# ST_LINK_V2-1.net
KiCad netlist of a schematic drawn in Altium Designer
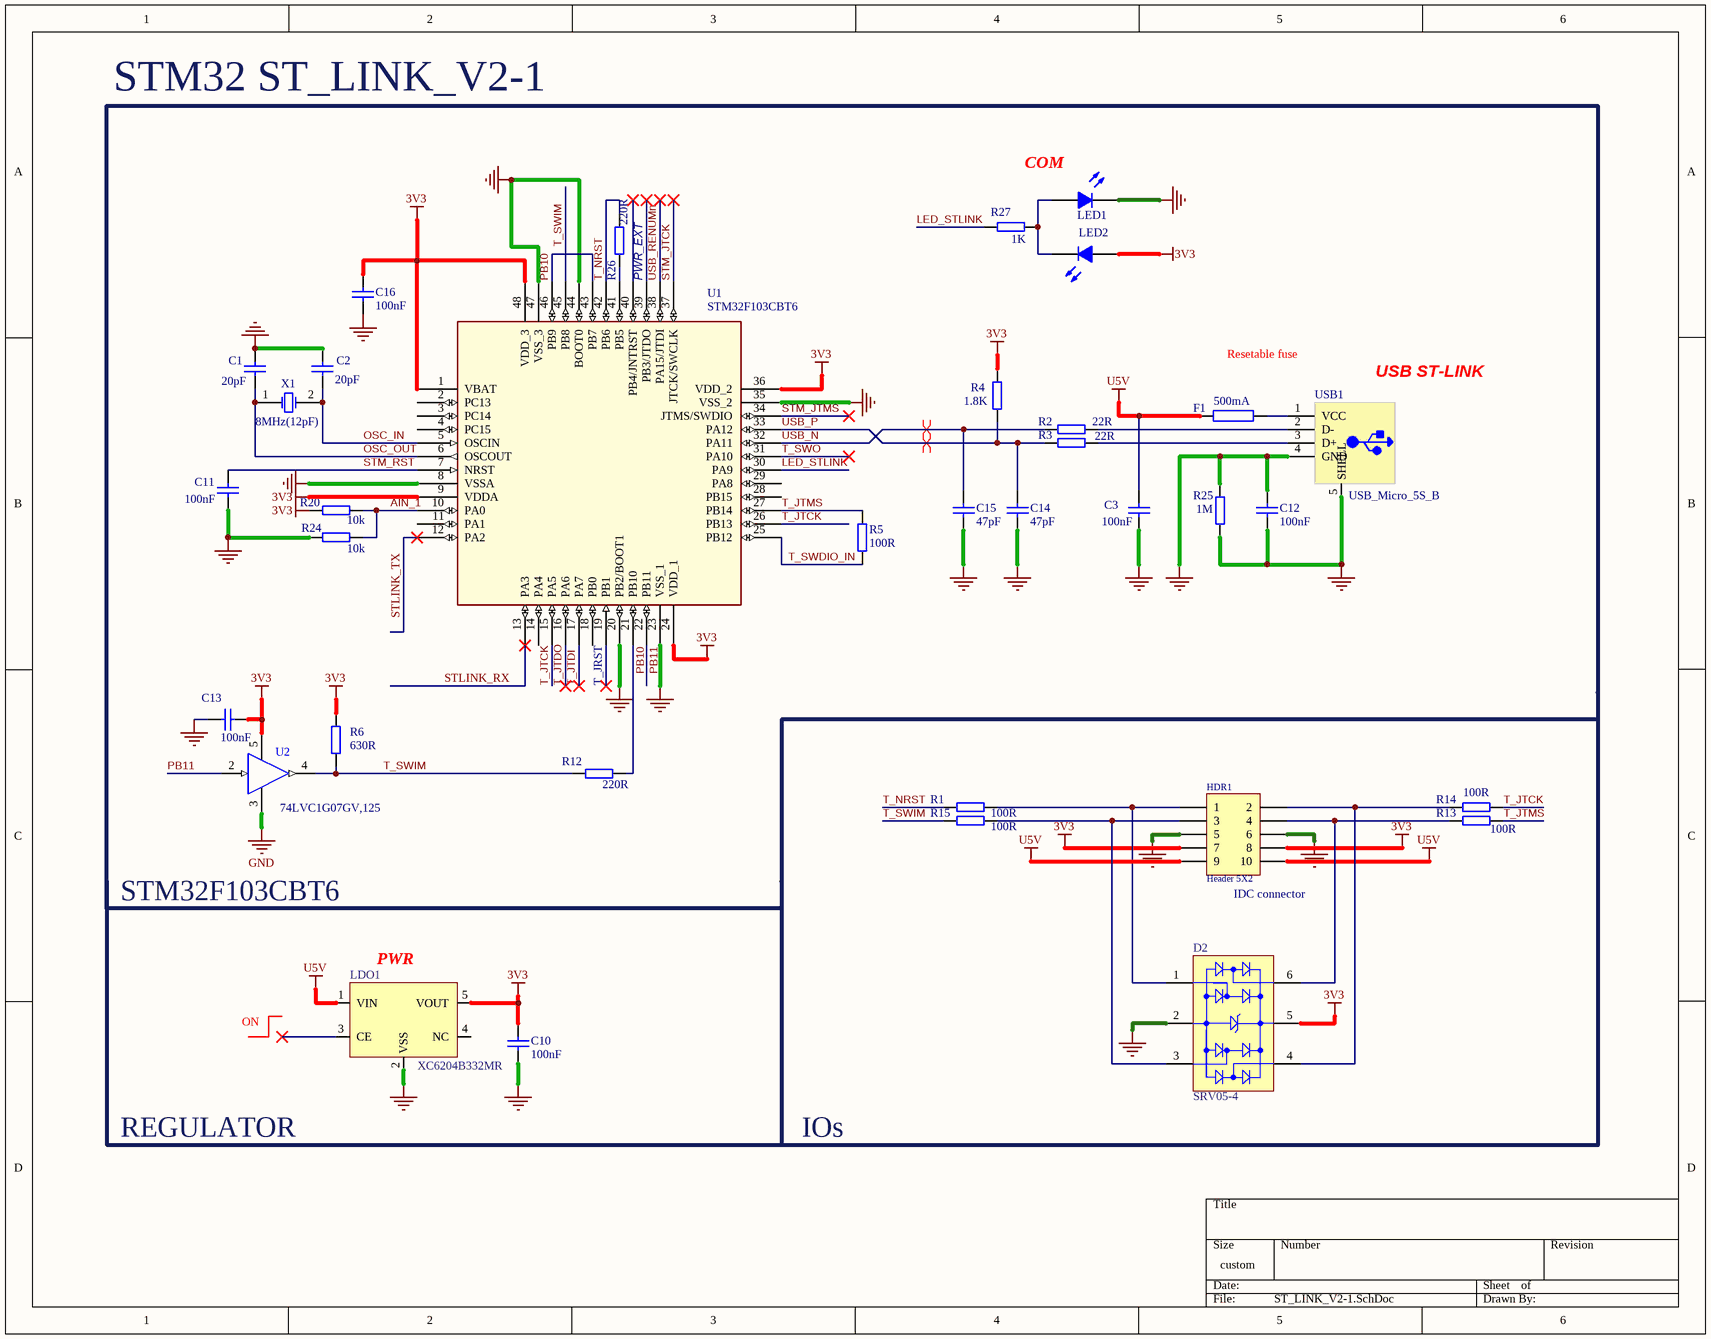
[diagram p0: ST_LINK_V2-1.SchDoc]

(export (version "E")
  (design (tool "Eeschema 10.0.6"))
  (components
    (comp (ref "C1")
      (value "20pF")
      (footprint "C0603-NO")
      (description "Capacitor, X5R, ±10%, 6.3V")
      (fields
        (field (name "PART NUMBER") "C0603-N.C.")
        (field (name "MANUFACTURER") "N.A.")
        (field (name "PUBLISHER") "Nordic Semiconductor")
      )
      (libsource (lib "adafruit") (part "Cap_0603"))
    )
    (comp (ref "C2")
      (value "20pF")
      (footprint "C0603-NO")
      (description "Capacitor, X5R, ±10%, 6.3V")
      (fields
        (field (name "PART NUMBER") "C0603-N.C.")
        (field (name "MANUFACTURER") "N.A.")
        (field (name "PUBLISHER") "Nordic Semiconductor")
      )
      (libsource (lib "adafruit") (part "Cap_0603"))
    )
    (comp (ref "C3")
      (value "100nF")
      (footprint "C0603-NO")
      (description "Capacitor, X5R, ±10%, 6.3V")
      (fields
        (field (name "PART NUMBER") "C0603-N.C.")
        (field (name "MANUFACTURER") "N.A.")
        (field (name "PUBLISHER") "Nordic Semiconductor")
      )
      (libsource (lib "adafruit") (part "Cap_0603"))
    )
    (comp (ref "C10")
      (value "100nF")
      (footprint "C0603-NO")
      (description "Capacitor, X5R, ±10%, 6.3V")
      (fields
        (field (name "PART NUMBER") "C0603-N.C.")
        (field (name "MANUFACTURER") "N.A.")
        (field (name "PUBLISHER") "Nordic Semiconductor")
      )
      (libsource (lib "adafruit") (part "Cap_0603"))
    )
    (comp (ref "C11")
      (value "100nF")
      (footprint "C0603-NO")
      (description "Capacitor, X5R, ±10%, 6.3V")
      (fields
        (field (name "PART NUMBER") "C0603-N.C.")
        (field (name "MANUFACTURER") "N.A.")
        (field (name "PUBLISHER") "Nordic Semiconductor")
      )
      (libsource (lib "adafruit") (part "Cap_0603"))
    )
    (comp (ref "C12")
      (value "100nF")
      (footprint "C0603-NO")
      (description "Capacitor, X5R, ±10%, 6.3V")
      (fields
        (field (name "PART NUMBER") "C0603-N.C.")
        (field (name "MANUFACTURER") "N.A.")
        (field (name "PUBLISHER") "Nordic Semiconductor")
      )
      (libsource (lib "adafruit") (part "Cap_0603"))
    )
    (comp (ref "C13")
      (value "100nF")
      (footprint "C0603-NO")
      (description "Capacitor, X5R, ±10%, 6.3V")
      (fields
        (field (name "PART NUMBER") "C0603-N.C.")
        (field (name "MANUFACTURER") "N.A.")
        (field (name "PUBLISHER") "Nordic Semiconductor")
      )
      (libsource (lib "adafruit") (part "Cap_0603"))
    )
    (comp (ref "C14")
      (value "47pF")
      (footprint "C0603-NO")
      (description "Capacitor, X5R, ±10%, 6.3V")
      (fields
        (field (name "PART NUMBER") "C0603-N.C.")
        (field (name "MANUFACTURER") "N.A.")
        (field (name "PUBLISHER") "Nordic Semiconductor")
      )
      (libsource (lib "adafruit") (part "Cap_0603"))
    )
    (comp (ref "C15")
      (value "47pF")
      (footprint "C0603-NO")
      (description "Capacitor, X5R, ±10%, 6.3V")
      (fields
        (field (name "PART NUMBER") "C0603-N.C.")
        (field (name "MANUFACTURER") "N.A.")
        (field (name "PUBLISHER") "Nordic Semiconductor")
      )
      (libsource (lib "adafruit") (part "Cap_0603"))
    )
    (comp (ref "C16")
      (value "100nF")
      (footprint "C0603-NO")
      (description "Capacitor, X5R, ±10%, 6.3V")
      (fields
        (field (name "PART NUMBER") "C0603-N.C.")
        (field (name "MANUFACTURER") "N.A.")
        (field (name "PUBLISHER") "Nordic Semiconductor")
      )
      (libsource (lib "adafruit") (part "Cap_0603"))
    )
    (comp (ref "D2")
      (value "SRV05-4")
      (footprint "SOT23-6")
      (fields (field (name "MANUFACTURER") "MSKSEMI(美森科)"))
      (libsource (lib "adafruit") (part "SRV05-4"))
    )
    (comp (ref "F1")
      (value "500mA")
      (footprint "F1206")
      (description "Resetable fuse")
      (fields (field (name "Comment") "Resistor_FUSE"))
      (libsource (lib "adafruit") (part "Resistor_FUSE"))
    )
    (comp (ref "HDR1")
      (value "Header 5X2")
      (footprint "IDC10_2SIDED")
      (description "Header, 5-Pin, Dual row")
      (libsource (lib "adafruit") (part "Header 5X2"))
    )
    (comp (ref "LDO1")
      (value "XC6204B332MR")
      (footprint "SOT23-5L")
      (fields (field (name "MANUFACTURER") "TOREX(特瑞仕)"))
      (libsource (lib "adafruit") (part "XC6204B332MR"))
    )
    (comp (ref "LED1")
      (value "GREEN LED")
      (footprint "CHIPLED_0603 - NO")
      (description "SMD lamp beads")
      (libsource (lib "adafruit") (part "LEDCHIP-LED0603"))
    )
    (comp (ref "LED2")
      (value "BLUE LED")
      (footprint "CHIPLED_0603 - NO")
      (description "SMD lamp beads")
      (libsource (lib "adafruit") (part "LEDCHIP-LED0603"))
    )
    (comp (ref "R1")
      (value "100Ω")
      (footprint "R0603-NO")
      (description "Resistor, ±1%, 0.100W")
      (fields
        (field (name "PART NUMBER") "R0603-N.C.Ω")
        (field (name "MANUFACTURER") "N.A.")
        (field (name "PUBLISHER") "Nordic Semiconductor")
      )
      (libsource (lib "adafruit") (part "Res_0603"))
    )
    (comp (ref "R2")
      (value "22Ω")
      (footprint "R0603-NO")
      (description "Resistor, ±1%, 0.100W")
      (fields
        (field (name "PART NUMBER") "R0603-N.C.Ω")
        (field (name "MANUFACTURER") "N.A.")
        (field (name "PUBLISHER") "Nordic Semiconductor")
      )
      (libsource (lib "") (part "Res_0603_2"))
    )
    (comp (ref "R3")
      (value "22Ω")
      (footprint "R0603-NO")
      (description "Resistor, ±1%, 0.100W")
      (fields
        (field (name "PART NUMBER") "R0603-N.C.Ω")
        (field (name "MANUFACTURER") "N.A.")
        (field (name "PUBLISHER") "Nordic Semiconductor")
      )
      (libsource (lib "") (part "Res_0603_2"))
    )
    (comp (ref "R4")
      (value "1.8kΩ")
      (footprint "R0603-NO")
      (description "Resistor, ±1%, 0.100W")
      (fields
        (field (name "PART NUMBER") "R0603-N.C.Ω")
        (field (name "MANUFACTURER") "N.A.")
        (field (name "PUBLISHER") "Nordic Semiconductor")
      )
      (libsource (lib "adafruit") (part "Res_0603"))
    )
    (comp (ref "R5")
      (value "100Ω")
      (footprint "R0603-NO")
      (description "Resistor, ±1%, 0.100W")
      (fields
        (field (name "PART NUMBER") "R0603-N.C.Ω")
        (field (name "MANUFACTURER") "N.A.")
        (field (name "PUBLISHER") "Nordic Semiconductor")
      )
      (libsource (lib "") (part "Res_0603_3"))
    )
    (comp (ref "R6")
      (value "630Ω")
      (footprint "R0603-NO")
      (description "Resistor, ±1%, 0.100W")
      (fields
        (field (name "PART NUMBER") "R0603-N.C.Ω")
        (field (name "MANUFACTURER") "N.A.")
        (field (name "PUBLISHER") "Nordic Semiconductor")
      )
      (libsource (lib "") (part "Res_0603_1"))
    )
    (comp (ref "R12")
      (value "220Ω")
      (footprint "R0603-NO")
      (description "Resistor, ±1%, 0.100W")
      (fields
        (field (name "PART NUMBER") "R0603-N.C.Ω")
        (field (name "MANUFACTURER") "N.A.")
        (field (name "PUBLISHER") "Nordic Semiconductor")
      )
      (libsource (lib "") (part "Res_0603_3"))
    )
    (comp (ref "R13")
      (value "100Ω")
      (footprint "R0603-NO")
      (description "Resistor, ±1%, 0.100W")
      (fields
        (field (name "PART NUMBER") "R0603-N.C.Ω")
        (field (name "MANUFACTURER") "N.A.")
        (field (name "PUBLISHER") "Nordic Semiconductor")
      )
      (libsource (lib "") (part "Res_0603_1"))
    )
    (comp (ref "R14")
      (value "100Ω")
      (footprint "R0603-NO")
      (description "Resistor, ±1%, 0.100W")
      (fields
        (field (name "PART NUMBER") "R0603-N.C.Ω")
        (field (name "MANUFACTURER") "N.A.")
        (field (name "PUBLISHER") "Nordic Semiconductor")
      )
      (libsource (lib "") (part "Res_0603_2"))
    )
    (comp (ref "R15")
      (value "100Ω")
      (footprint "R0603-NO")
      (description "Resistor, ±1%, 0.100W")
      (fields
        (field (name "PART NUMBER") "R0603-N.C.Ω")
        (field (name "MANUFACTURER") "N.A.")
        (field (name "PUBLISHER") "Nordic Semiconductor")
      )
      (libsource (lib "") (part "Res_0603_2"))
    )
    (comp (ref "R20")
      (value "10kΩ")
      (footprint "R0603-NO")
      (description "Resistor, ±1%, 0.100W")
      (fields
        (field (name "PART NUMBER") "R0603-N.C.Ω")
        (field (name "MANUFACTURER") "N.A.")
        (field (name "PUBLISHER") "Nordic Semiconductor")
      )
      (libsource (lib "") (part "Res_0603_3"))
    )
    (comp (ref "R24")
      (value "10kΩ")
      (footprint "R0603-NO")
      (description "Resistor, ±1%, 0.100W")
      (fields
        (field (name "PART NUMBER") "R0603-N.C.Ω")
        (field (name "MANUFACTURER") "N.A.")
        (field (name "PUBLISHER") "Nordic Semiconductor")
      )
      (libsource (lib "adafruit") (part "Res_0603"))
    )
    (comp (ref "R25")
      (value "1MΩ")
      (footprint "R0603-NO")
      (description "Resistor, ±1%, 0.100W")
      (fields
        (field (name "PART NUMBER") "R0603-N.C.Ω")
        (field (name "MANUFACTURER") "N.A.")
        (field (name "PUBLISHER") "Nordic Semiconductor")
      )
      (libsource (lib "") (part "Res_0603_1"))
    )
    (comp (ref "R26")
      (value "220Ω")
      (footprint "R0603-NO")
      (description "Resistor, ±1%, 0.100W")
      (fields
        (field (name "PART NUMBER") "R0603-N.C.Ω")
        (field (name "MANUFACTURER") "N.A.")
        (field (name "PUBLISHER") "Nordic Semiconductor")
      )
      (libsource (lib "") (part "Res_0603_1"))
    )
    (comp (ref "R27")
      (value "1kΩ")
      (footprint "R0603-NO")
      (description "Resistor, ±1%, 0.100W")
      (fields
        (field (name "PART NUMBER") "R0603-N.C.Ω")
        (field (name "MANUFACTURER") "N.A.")
        (field (name "PUBLISHER") "Nordic Semiconductor")
      )
      (libsource (lib "adafruit") (part "Res_0603"))
    )
    (comp (ref "U1")
      (value "STM32F103CBT6")
      (footprint "QFP48 7X7")
      (description "Medium-density performance line ARM-based 32-bit MCU with 64KB Flash")
      (libsource (lib "Nucleo_64") (part "STM32F103CBT6"))
    )
    (comp (ref "U2")
      (value "74LVC1G07GV,125")
      (footprint "SOT23-5L")
      (fields (field (name "MANUFACTURER") "Nexperia(安世)"))
      (libsource (lib "adafruit") (part "74LVC1G07GV,125"))
    )
    (comp (ref "USB1")
      (value "USB ConnectorsUSBMINIB - Surface Mount Female Mini-B USB Connector 4UConnector: 06564   By microbuilder.euThru-hole RA Female Mini-B USB Connector 4UConnector: 18732   By ladyada.net")
      (footprint "USB-A-SMT_48037-0001")
      (fields (field (name "NAME") "USB_Micro_5S_B"))
      (libsource (lib "adafruit") (part "USB-MALE"))
    )
    (comp (ref "X1")
      (value "8MHz(12pF)")
      (footprint "XTAL1")
      (description "Crystal Oscillator")
      (fields (field (name "PUBLISHER") "Altium Limited"))
      (libsource (lib "MB963_1") (part "XTAL"))
    )
  )
  (nets
    (net (code "1") (name "/AIN_1") (class "Default")
      (node (ref "R20") (pin "2") (pinfunction "2_2") (pintype "passive"))
      (node (ref "R24") (pin "1") (pinfunction "1_1") (pintype "passive"))
      (node (ref "U1") (pin "10") (pinfunction "PA0_10") (pintype "bidirectional"))
    )
    (net (code "2") (name "/LED_STLINK") (class "Default")
      (node (ref "R27") (pin "2") (pinfunction "2_2") (pintype "passive"))
      (node (ref "U1") (pin "30") (pinfunction "PA9_30") (pintype "bidirectional"))
    )
    (net (code "3") (name "/OSC_IN") (class "Default")
      (node (ref "C2") (pin "1") (pinfunction "1_1") (pintype "passive"))
      (node (ref "U1") (pin "5") (pinfunction "OSCIN_5") (pintype "input"))
      (node (ref "X1") (pin "2") (pinfunction "OSC2_2") (pintype "passive"))
    )
    (net (code "4") (name "/OSC_OUT") (class "Default")
      (node (ref "C1") (pin "1") (pinfunction "1_1") (pintype "passive"))
      (node (ref "U1") (pin "6") (pinfunction "OSCOUT_6") (pintype "output"))
      (node (ref "X1") (pin "1") (pinfunction "OSC1_1") (pintype "passive"))
    )
    (net (code "5") (name "/PB10") (class "Default")
      (node (ref "R12") (pin "2") (pinfunction "2_2") (pintype "passive"))
      (node (ref "U1") (pin "21") (pinfunction "PB10_21") (pintype "bidirectional"))
      (node (ref "U1") (pin "43") (pinfunction "PB7_43") (pintype "bidirectional"))
      (node (ref "U1") (pin "46") (pinfunction "PB9_46") (pintype "bidirectional"))
    )
    (net (code "6") (name "/PB11") (class "Default")
      (node (ref "U1") (pin "22") (pinfunction "PB11_22") (pintype "bidirectional"))
      (node (ref "U2") (pin "2") (pinfunction "A_2") (pintype "input"))
    )
    (net (code "7") (name "/STLINK_RX") (class "Default")
      (node (ref "U1") (pin "13") (pinfunction "PA3_13") (pintype "bidirectional+no_connect"))
    )
    (net (code "8") (name "/STLINK_TX") (class "Default")
      (node (ref "U1") (pin "12") (pinfunction "PA2_12") (pintype "bidirectional+no_connect"))
    )
    (net (code "9") (name "/STM_JTCK") (class "Default")
      (node (ref "U1") (pin "37") (pinfunction "JTCK/SWCLK_37") (pintype "bidirectional+no_connect"))
    )
    (net (code "10") (name "/STM_JTMS") (class "Default")
      (node (ref "U1") (pin "34") (pinfunction "JTMS/SWDIO_34") (pintype "bidirectional+no_connect"))
    )
    (net (code "11") (name "/STM_RST") (class "Default")
      (node (ref "C11") (pin "2") (pinfunction "2_2") (pintype "passive"))
      (node (ref "U1") (pin "7") (pinfunction "NRST_7") (pintype "input"))
    )
    (net (code "12") (name "/T_JTCK") (class "Default")
      (node (ref "R14") (pin "2") (pinfunction "2_2") (pintype "passive"))
      (node (ref "U1") (pin "15") (pinfunction "PA5_15") (pintype "bidirectional"))
      (node (ref "U1") (pin "26") (pinfunction "PB13_26") (pintype "bidirectional"))
    )
    (net (code "13") (name "/T_JTDI") (class "Default")
      (node (ref "U1") (pin "17") (pinfunction "PA7_17") (pintype "bidirectional+no_connect"))
    )
    (net (code "14") (name "/T_JTDO") (class "Default")
      (node (ref "U1") (pin "16") (pinfunction "PA6_16") (pintype "bidirectional+no_connect"))
    )
    (net (code "15") (name "/T_JTMS") (class "Default")
      (node (ref "R13") (pin "1") (pinfunction "1_1") (pintype "passive"))
      (node (ref "R5") (pin "2") (pinfunction "2_2") (pintype "passive"))
      (node (ref "U1") (pin "27") (pinfunction "PB14_27") (pintype "bidirectional"))
    )
    (net (code "16") (name "/T_NRST") (class "Default")
      (node (ref "R1") (pin "2") (pinfunction "2_2") (pintype "passive"))
      (node (ref "R26") (pin "1") (pinfunction "1_1") (pintype "passive"))
      (node (ref "U1") (pin "42") (pinfunction "PB6_42") (pintype "bidirectional"))
    )
    (net (code "17") (name "/T_SWDIO_IN") (class "Default")
      (node (ref "R5") (pin "1") (pinfunction "1_1") (pintype "passive"))
      (node (ref "U1") (pin "25") (pinfunction "PB12_25") (pintype "bidirectional"))
    )
    (net (code "18") (name "/T_SWIM") (class "Default")
      (node (ref "R12") (pin "1") (pinfunction "1_1") (pintype "passive"))
      (node (ref "R15") (pin "1") (pinfunction "1_1") (pintype "passive"))
      (node (ref "R6") (pin "2") (pinfunction "2_2") (pintype "passive"))
      (node (ref "U1") (pin "45") (pinfunction "PB8_45") (pintype "bidirectional"))
      (node (ref "U2") (pin "4") (pinfunction "Y_4") (pintype "output"))
    )
    (net (code "19") (name "/T_SWO") (class "Default")
      (node (ref "U1") (pin "31") (pinfunction "PA10_31") (pintype "bidirectional+no_connect"))
    )
    (net (code "20") (name "/USB_N") (class "Default")
      (node (ref "C15") (pin "2") (pinfunction "2_2") (pintype "passive"))
      (node (ref "R2") (pin "1") (pinfunction "1_1") (pintype "passive"))
      (node (ref "U1") (pin "32") (pinfunction "PA11_32") (pintype "bidirectional"))
    )
    (net (code "21") (name "/USB_P") (class "Default")
      (node (ref "C14") (pin "2") (pinfunction "2_2") (pintype "passive"))
      (node (ref "R3") (pin "1") (pinfunction "1_1") (pintype "passive"))
      (node (ref "R4") (pin "2") (pinfunction "2_2") (pintype "passive"))
      (node (ref "U1") (pin "33") (pinfunction "PA12_33") (pintype "bidirectional"))
    )
    (net (code "22") (name "/USB_RENUMn") (class "Default")
      (node (ref "U1") (pin "38") (pinfunction "PA15/JTDI_38") (pintype "bidirectional+no_connect"))
    )
    (net (code "23") (name "3V3") (class "Default")
      (node (ref "C10") (pin "2") (pinfunction "2_2") (pintype "passive"))
      (node (ref "C13") (pin "2") (pinfunction "2_2") (pintype "passive"))
      (node (ref "C16") (pin "2") (pinfunction "2_2") (pintype "passive"))
      (node (ref "D2") (pin "5") (pinfunction "VBUS_5") (pintype "passive"))
      (node (ref "HDR1") (pin "7") (pinfunction "7_7") (pintype "passive"))
      (node (ref "HDR1") (pin "8") (pinfunction "8_8") (pintype "passive"))
      (node (ref "LDO1") (pin "5") (pinfunction "VOUT_5") (pintype "passive"))
      (node (ref "LED2") (pin "A") (pinfunction "A_A") (pintype "passive"))
      (node (ref "R20") (pin "1") (pinfunction "1_1") (pintype "passive"))
      (node (ref "R4") (pin "1") (pinfunction "1_1") (pintype "passive"))
      (node (ref "R6") (pin "1") (pinfunction "1_1") (pintype "passive"))
      (node (ref "U1") (pin "1") (pinfunction "VBAT_1") (pintype "power_in"))
      (node (ref "U1") (pin "24") (pinfunction "VDD_1_24") (pintype "power_in"))
      (node (ref "U1") (pin "36") (pinfunction "VDD_2_36") (pintype "power_in"))
      (node (ref "U1") (pin "48") (pinfunction "VDD_3_48") (pintype "power_in"))
      (node (ref "U1") (pin "9") (pinfunction "VDDA_9") (pintype "power_in"))
      (node (ref "U2") (pin "5") (pinfunction "VCC_5") (pintype "passive"))
    )
    (net (code "24") (name "GND") (class "Default")
      (node (ref "C1") (pin "2") (pinfunction "2_2") (pintype "passive"))
      (node (ref "C10") (pin "1") (pinfunction "1_1") (pintype "passive"))
      (node (ref "C11") (pin "1") (pinfunction "1_1") (pintype "passive"))
      (node (ref "C12") (pin "1") (pinfunction "1_1") (pintype "passive"))
      (node (ref "C13") (pin "1") (pinfunction "1_1") (pintype "passive"))
      (node (ref "C14") (pin "1") (pinfunction "1_1") (pintype "passive"))
      (node (ref "C15") (pin "1") (pinfunction "1_1") (pintype "passive"))
      (node (ref "C16") (pin "1") (pinfunction "1_1") (pintype "passive"))
      (node (ref "C2") (pin "2") (pinfunction "2_2") (pintype "passive"))
      (node (ref "C3") (pin "1") (pinfunction "1_1") (pintype "passive"))
      (node (ref "D2") (pin "2") (pinfunction "GND_2") (pintype "passive"))
      (node (ref "HDR1") (pin "5") (pinfunction "5_5") (pintype "passive"))
      (node (ref "HDR1") (pin "6") (pinfunction "6_6") (pintype "passive"))
      (node (ref "LDO1") (pin "2") (pinfunction "VSS_2") (pintype "passive"))
      (node (ref "LED1") (pin "C") (pinfunction "K_C") (pintype "passive"))
      (node (ref "R24") (pin "2") (pinfunction "2_2") (pintype "passive"))
      (node (ref "R25") (pin "1") (pinfunction "1_1") (pintype "passive"))
      (node (ref "U1") (pin "20") (pinfunction "PB2/BOOT1_20") (pintype "bidirectional"))
      (node (ref "U1") (pin "23") (pinfunction "VSS_1_23") (pintype "power_in"))
      (node (ref "U1") (pin "35") (pinfunction "VSS_2_35") (pintype "power_in"))
      (node (ref "U1") (pin "44") (pinfunction "BOOT0_44") (pintype "bidirectional"))
      (node (ref "U1") (pin "47") (pinfunction "VSS_3_47") (pintype "power_in"))
      (node (ref "U1") (pin "8") (pinfunction "VSSA_8") (pintype "power_in"))
      (node (ref "U2") (pin "3") (pinfunction "GND_3") (pintype "passive"))
      (node (ref "USB1") (pin "4") (pinfunction "GND_4") (pintype "passive"))
    )
    (net (code "25") (name "GND1") (class "Default")
      (node (ref "C12") (pin "2") (pinfunction "2_2") (pintype "passive"))
      (node (ref "R25") (pin "2") (pinfunction "2_2") (pintype "passive"))
      (node (ref "USB1") (pin "5") (pinfunction "SHELL_5") (pintype "power_in"))
    )
    (net (code "26") (name "Net-(D2-I{slash}O_1)") (class "Default")
      (node (ref "D2") (pin "1") (pinfunction "I/O_1_1") (pintype "passive"))
      (node (ref "HDR1") (pin "1") (pinfunction "1_1") (pintype "passive"))
      (node (ref "R1") (pin "1") (pinfunction "1_1") (pintype "passive"))
    )
    (net (code "27") (name "Net-(D2-I{slash}O_2)") (class "Default")
      (node (ref "D2") (pin "3") (pinfunction "I/O_2_3") (pintype "passive"))
      (node (ref "HDR1") (pin "3") (pinfunction "3_3") (pintype "passive"))
      (node (ref "R15") (pin "2") (pinfunction "2_2") (pintype "passive"))
    )
    (net (code "28") (name "Net-(D2-I{slash}O_3)") (class "Default")
      (node (ref "D2") (pin "4") (pinfunction "I/O_3_4") (pintype "passive"))
      (node (ref "HDR1") (pin "2") (pinfunction "2_2") (pintype "passive"))
      (node (ref "R14") (pin "1") (pinfunction "1_1") (pintype "passive"))
    )
    (net (code "29") (name "Net-(D2-I{slash}O_4)") (class "Default")
      (node (ref "D2") (pin "6") (pinfunction "I/O_4_6") (pintype "passive"))
      (node (ref "HDR1") (pin "4") (pinfunction "4_4") (pintype "passive"))
      (node (ref "R13") (pin "2") (pinfunction "2_2") (pintype "passive"))
    )
    (net (code "30") (name "Net-(LED2-K)") (class "Default")
      (node (ref "LED1") (pin "A") (pinfunction "A_A") (pintype "passive"))
      (node (ref "LED2") (pin "C") (pinfunction "K_C") (pintype "passive"))
      (node (ref "R27") (pin "1") (pinfunction "1_1") (pintype "passive"))
    )
    (net (code "31") (name "Net-(U1-PB5)") (class "Default")
      (node (ref "R26") (pin "2") (pinfunction "2_2") (pintype "passive"))
      (node (ref "U1") (pin "41") (pinfunction "PB5_41") (pintype "bidirectional"))
    )
    (net (code "32") (name "Net-(USB1-D+)") (class "Default")
      (node (ref "R3") (pin "2") (pinfunction "2_2") (pintype "passive"))
      (node (ref "USB1") (pin "3") (pinfunction "D+_3") (pintype "passive"))
    )
    (net (code "33") (name "Net-(USB1-D-)") (class "Default")
      (node (ref "R2") (pin "2") (pinfunction "2_2") (pintype "passive"))
      (node (ref "USB1") (pin "2") (pinfunction "D-_2") (pintype "passive"))
    )
    (net (code "34") (name "Net-(USB1-VCC)") (class "Default")
      (node (ref "F1") (pin "1") (pinfunction "1_1") (pintype "passive"))
      (node (ref "USB1") (pin "1") (pinfunction "VCC_1") (pintype "power_in"))
    )
    (net (code "35") (name "U5V") (class "Default")
      (node (ref "C3") (pin "2") (pinfunction "2_2") (pintype "passive"))
      (node (ref "F1") (pin "2") (pinfunction "2_2") (pintype "passive"))
      (node (ref "HDR1") (pin "10") (pinfunction "10_10") (pintype "passive"))
      (node (ref "HDR1") (pin "9") (pinfunction "9_9") (pintype "passive"))
      (node (ref "LDO1") (pin "1") (pinfunction "VIN_1") (pintype "passive"))
    )
    (net (code "36") (name "unconnected-(LDO1-CE-Pad3)") (class "Default")
      (node (ref "LDO1") (pin "3") (pinfunction "CE_3") (pintype "passive+no_connect"))
    )
    (net (code "37") (name "unconnected-(LDO1-NC-Pad4)") (class "Default")
      (node (ref "LDO1") (pin "4") (pinfunction "NC_4") (pintype "passive"))
    )
    (net (code "38") (name "unconnected-(U1-PA1-Pad11)") (class "Default")
      (node (ref "U1") (pin "11") (pinfunction "PA1_11") (pintype "bidirectional"))
    )
    (net (code "39") (name "unconnected-(U1-PA4-Pad14)") (class "Default")
      (node (ref "U1") (pin "14") (pinfunction "PA4_14") (pintype "bidirectional"))
    )
    (net (code "40") (name "unconnected-(U1-PA8-Pad29)") (class "Default")
      (node (ref "U1") (pin "29") (pinfunction "PA8_29") (pintype "bidirectional"))
    )
    (net (code "41") (name "unconnected-(U1-PB0-Pad18)") (class "Default")
      (node (ref "U1") (pin "18") (pinfunction "PB0_18") (pintype "bidirectional"))
    )
    (net (code "42") (name "unconnected-(U1-PB1-Pad19)") (class "Default")
      (node (ref "U1") (pin "19") (pinfunction "PB1_19") (pintype "input+no_connect"))
    )
    (net (code "43") (name "unconnected-(U1-PB3{slash}JTDO-Pad39)") (class "Default")
      (node (ref "U1") (pin "39") (pinfunction "PB3/JTDO_39") (pintype "bidirectional+no_connect"))
    )
    (net (code "44") (name "unconnected-(U1-PB4{slash}JNTRST-Pad40)") (class "Default")
      (node (ref "U1") (pin "40") (pinfunction "PB4/JNTRST_40") (pintype "bidirectional+no_connect"))
    )
    (net (code "45") (name "unconnected-(U1-PB15-Pad28)") (class "Default")
      (node (ref "U1") (pin "28") (pinfunction "PB15_28") (pintype "bidirectional"))
    )
    (net (code "46") (name "unconnected-(U1-PC13-Pad2)") (class "Default")
      (node (ref "U1") (pin "2") (pinfunction "PC13_2") (pintype "bidirectional"))
    )
    (net (code "47") (name "unconnected-(U1-PC14-Pad3)") (class "Default")
      (node (ref "U1") (pin "3") (pinfunction "PC14_3") (pintype "bidirectional"))
    )
    (net (code "48") (name "unconnected-(U1-PC15-Pad4)") (class "Default")
      (node (ref "U1") (pin "4") (pinfunction "PC15_4") (pintype "bidirectional"))
    )
  )
)
